# Carte-Puissance.net
KiCad netlist of a schematic drawn in EAGLE
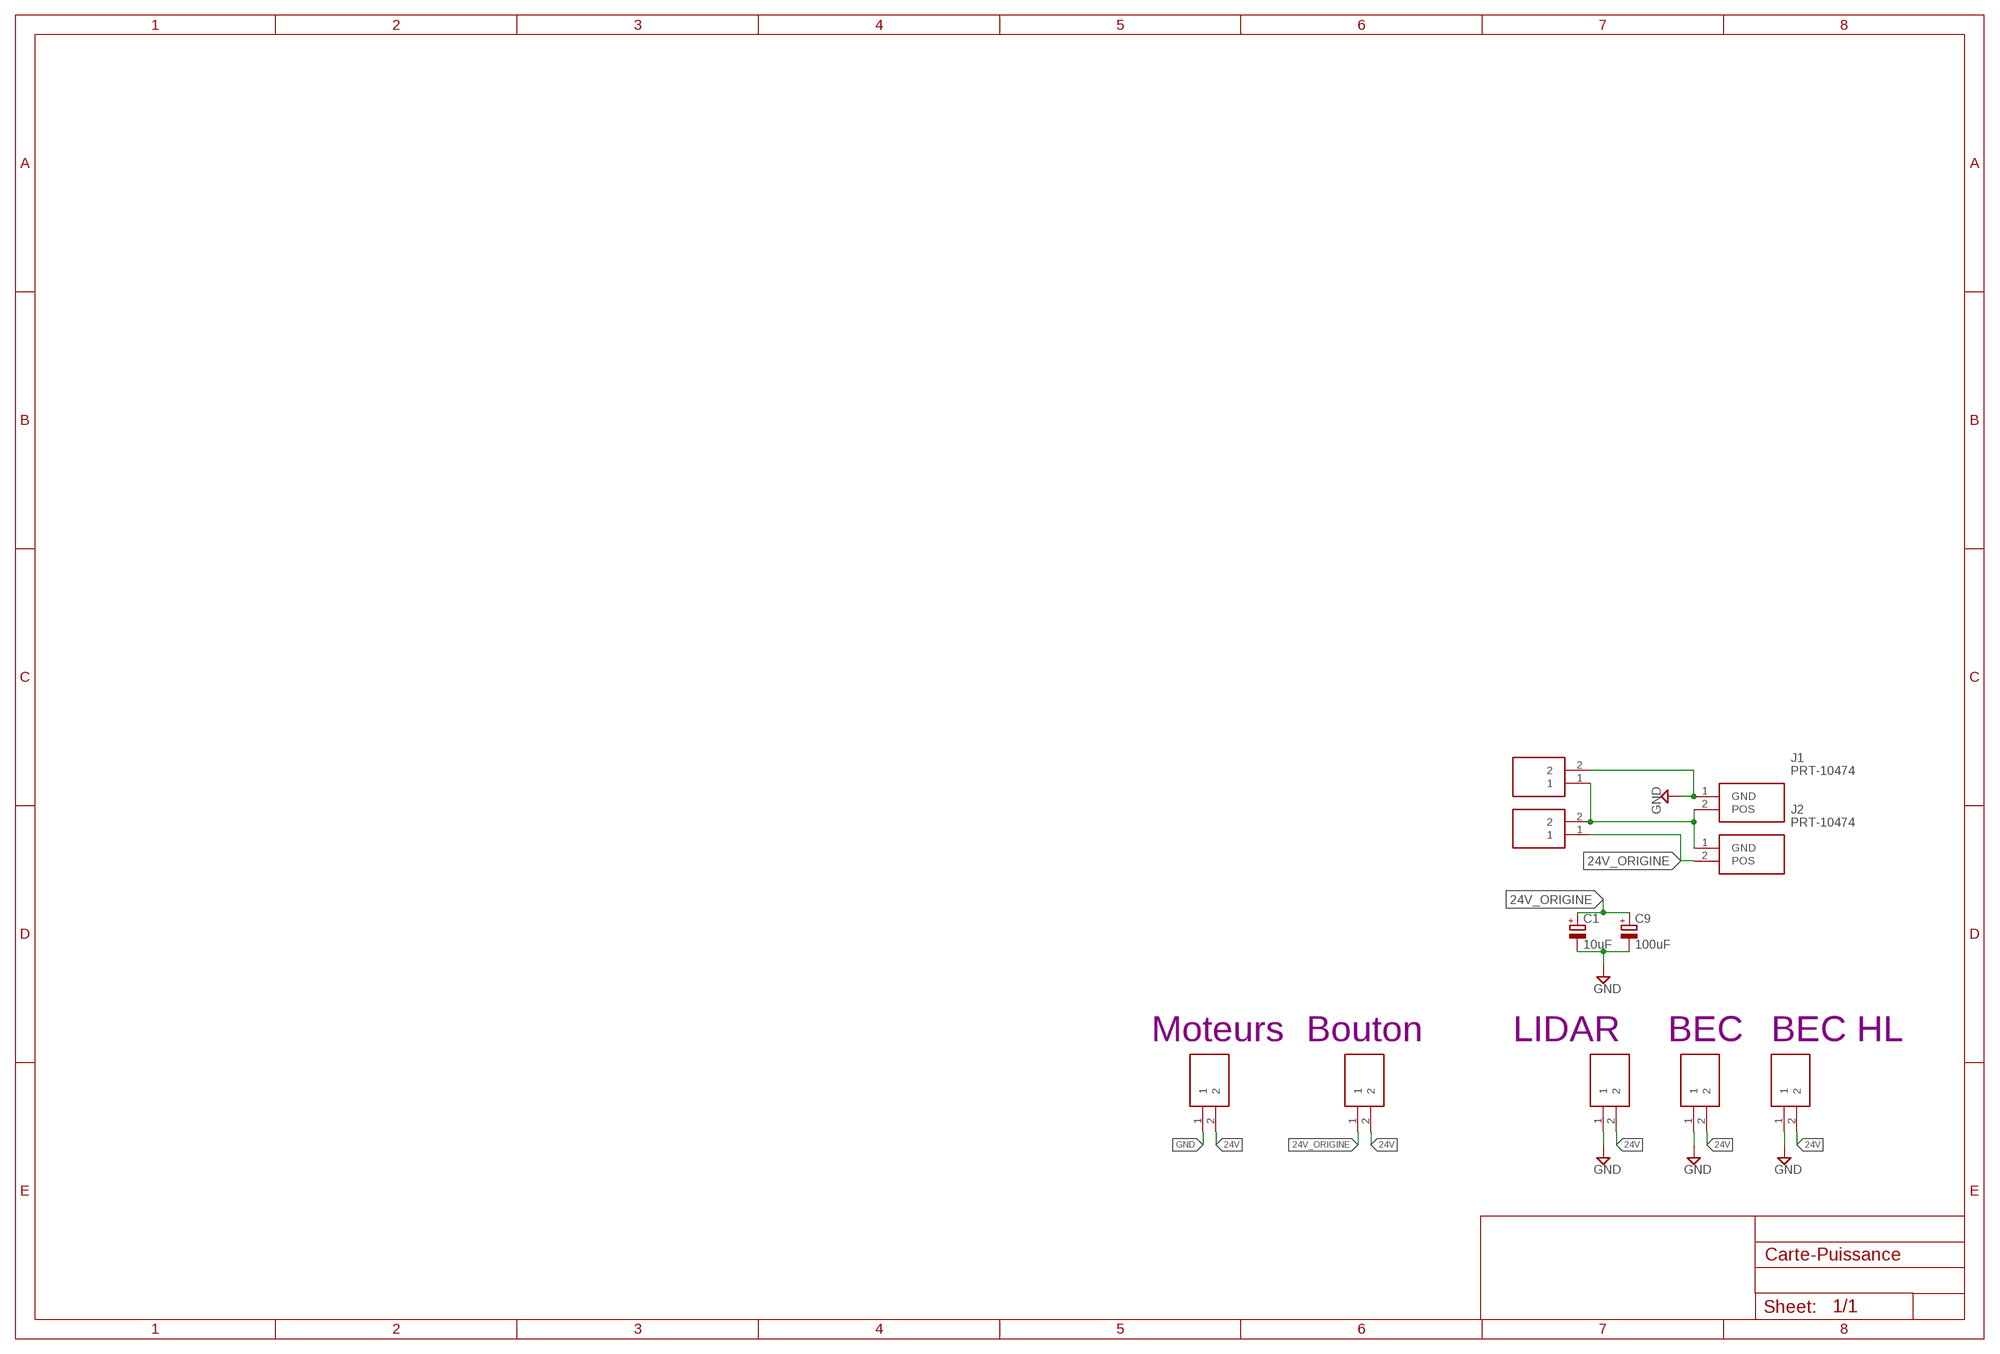
[diagram p0: schematic, sheet 1]

(export (version "E")
  (design (tool "Eeschema 10.0.6"))
  (components
    (comp (ref "C1")
      (value "10uF")
      (footprint "eagle-import:150CLZ-0810")
      (libsource (lib "eagle-import") (part "CPOL-EU150CLZ-0810"))
    )
    (comp (ref "C9")
      (value "100uF")
      (footprint "eagle-import:150CLZ-0810")
      (libsource (lib "eagle-import") (part "CPOL-EU150CLZ-0810"))
    )
    (comp (ref "J1")
      (value "PRT-10474")
      (footprint "eagle-import:SHDR2W320P716_1X2_1574X813X158")
      (fields (field (name "MOUSER_PART_NUMBER") "474-PRT-10474"))
      (libsource (lib "eagle-import") (part "PRT-10474"))
    )
    (comp (ref "J2")
      (value "PRT-10474")
      (footprint "eagle-import:SHDR2W320P716_1X2_1574X813X158")
      (fields (field (name "MOUSER_PART_NUMBER") "474-PRT-10474"))
      (libsource (lib "eagle-import") (part "PRT-10474"))
    )
    (comp (ref "J3")
      (value "B2P-VH(LF)(SN)")
      (footprint "eagle-import:SHDR2W114P0X396_1X2_786X850X94")
      (fields (field (name "RS_PART_NUMBER") "8201147P"))
      (libsource (lib "eagle-import") (part "B2P-VH(LF)(SN)"))
    )
    (comp (ref "J4")
      (value "B2P-VH(LF)(SN)")
      (footprint "eagle-import:SHDR2W114P0X396_1X2_786X850X94")
      (fields (field (name "RS_PART_NUMBER") "8201147P"))
      (libsource (lib "eagle-import") (part "B2P-VH(LF)(SN)"))
    )
    (comp (ref "J5")
      (value "B2P-VH(LF)(SN)")
      (footprint "eagle-import:SHDR2W114P0X396_1X2_786X850X94")
      (fields (field (name "RS_PART_NUMBER") "8201147P"))
      (libsource (lib "eagle-import") (part "B2P-VH(LF)(SN)"))
    )
    (comp (ref "J6")
      (value "B2P-VH(LF)(SN)")
      (footprint "eagle-import:SHDR2W114P0X396_1X2_786X850X94")
      (fields (field (name "RS_PART_NUMBER") "8201147P"))
      (libsource (lib "eagle-import") (part "B2P-VH(LF)(SN)"))
    )
    (comp (ref "J7")
      (value "B2P-VH(LF)(SN)")
      (footprint "eagle-import:SHDR2W114P0X396_1X2_786X850X94")
      (fields (field (name "RS_PART_NUMBER") "8201147P"))
      (libsource (lib "eagle-import") (part "B2P-VH(LF)(SN)"))
    )
    (comp (ref "J8")
      (value "B2P-VH(LF)(SN)")
      (footprint "eagle-import:SHDR2W114P0X396_1X2_786X850X94")
      (fields (field (name "RS_PART_NUMBER") "8201147P"))
      (libsource (lib "eagle-import") (part "B2P-VH(LF)(SN)"))
    )
    (comp (ref "J9")
      (value "B2P-VH(LF)(SN)")
      (footprint "eagle-import:SHDR2W114P0X396_1X2_786X850X94")
      (fields (field (name "RS_PART_NUMBER") "8201147P"))
      (libsource (lib "eagle-import") (part "B2P-VH(LF)(SN)"))
    )
  )
  (nets
    (net (code "1") (name "24V") (class "Default")
      (node (ref "J3") (pin "2") (pinfunction "2_2") (pintype "bidirectional"))
      (node (ref "J4") (pin "2") (pinfunction "2_2") (pintype "bidirectional"))
      (node (ref "J5") (pin "2") (pinfunction "2_2") (pintype "bidirectional"))
      (node (ref "J6") (pin "2") (pinfunction "2_2") (pintype "bidirectional"))
      (node (ref "J7") (pin "2") (pinfunction "2_2") (pintype "bidirectional"))
    )
    (net (code "2") (name "24V_ORIGINE") (class "Default")
      (node (ref "C1") (pin "+") (pinfunction "+_+") (pintype "passive"))
      (node (ref "C9") (pin "+") (pinfunction "+_+") (pintype "passive"))
      (node (ref "J2") (pin "2") (pinfunction "POS_2") (pintype "power_in"))
      (node (ref "J6") (pin "1") (pinfunction "1_1") (pintype "bidirectional"))
      (node (ref "J8") (pin "1") (pinfunction "1_1") (pintype "bidirectional"))
    )
    (net (code "3") (name "GND") (class "Default")
      (node (ref "C1") (pin "-") (pinfunction "-_-") (pintype "passive"))
      (node (ref "C9") (pin "-") (pinfunction "-_-") (pintype "passive"))
      (node (ref "J1") (pin "1") (pinfunction "GND_1") (pintype "power_in"))
      (node (ref "J3") (pin "1") (pinfunction "1_1") (pintype "bidirectional"))
      (node (ref "J4") (pin "1") (pinfunction "1_1") (pintype "bidirectional"))
      (node (ref "J5") (pin "1") (pinfunction "1_1") (pintype "bidirectional"))
      (node (ref "J7") (pin "1") (pinfunction "1_1") (pintype "bidirectional"))
      (node (ref "J9") (pin "2") (pinfunction "2_2") (pintype "bidirectional"))
    )
    (net (code "4") (name "Net-(J1-POS)") (class "Default")
      (node (ref "J1") (pin "2") (pinfunction "POS_2") (pintype "power_in"))
      (node (ref "J2") (pin "1") (pinfunction "GND_1") (pintype "power_in"))
      (node (ref "J8") (pin "2") (pinfunction "2_2") (pintype "bidirectional"))
      (node (ref "J9") (pin "1") (pinfunction "1_1") (pintype "bidirectional"))
    )
  )
)
